# USBHUB.net
KiCad netlist of a schematic drawn in Altium Designer
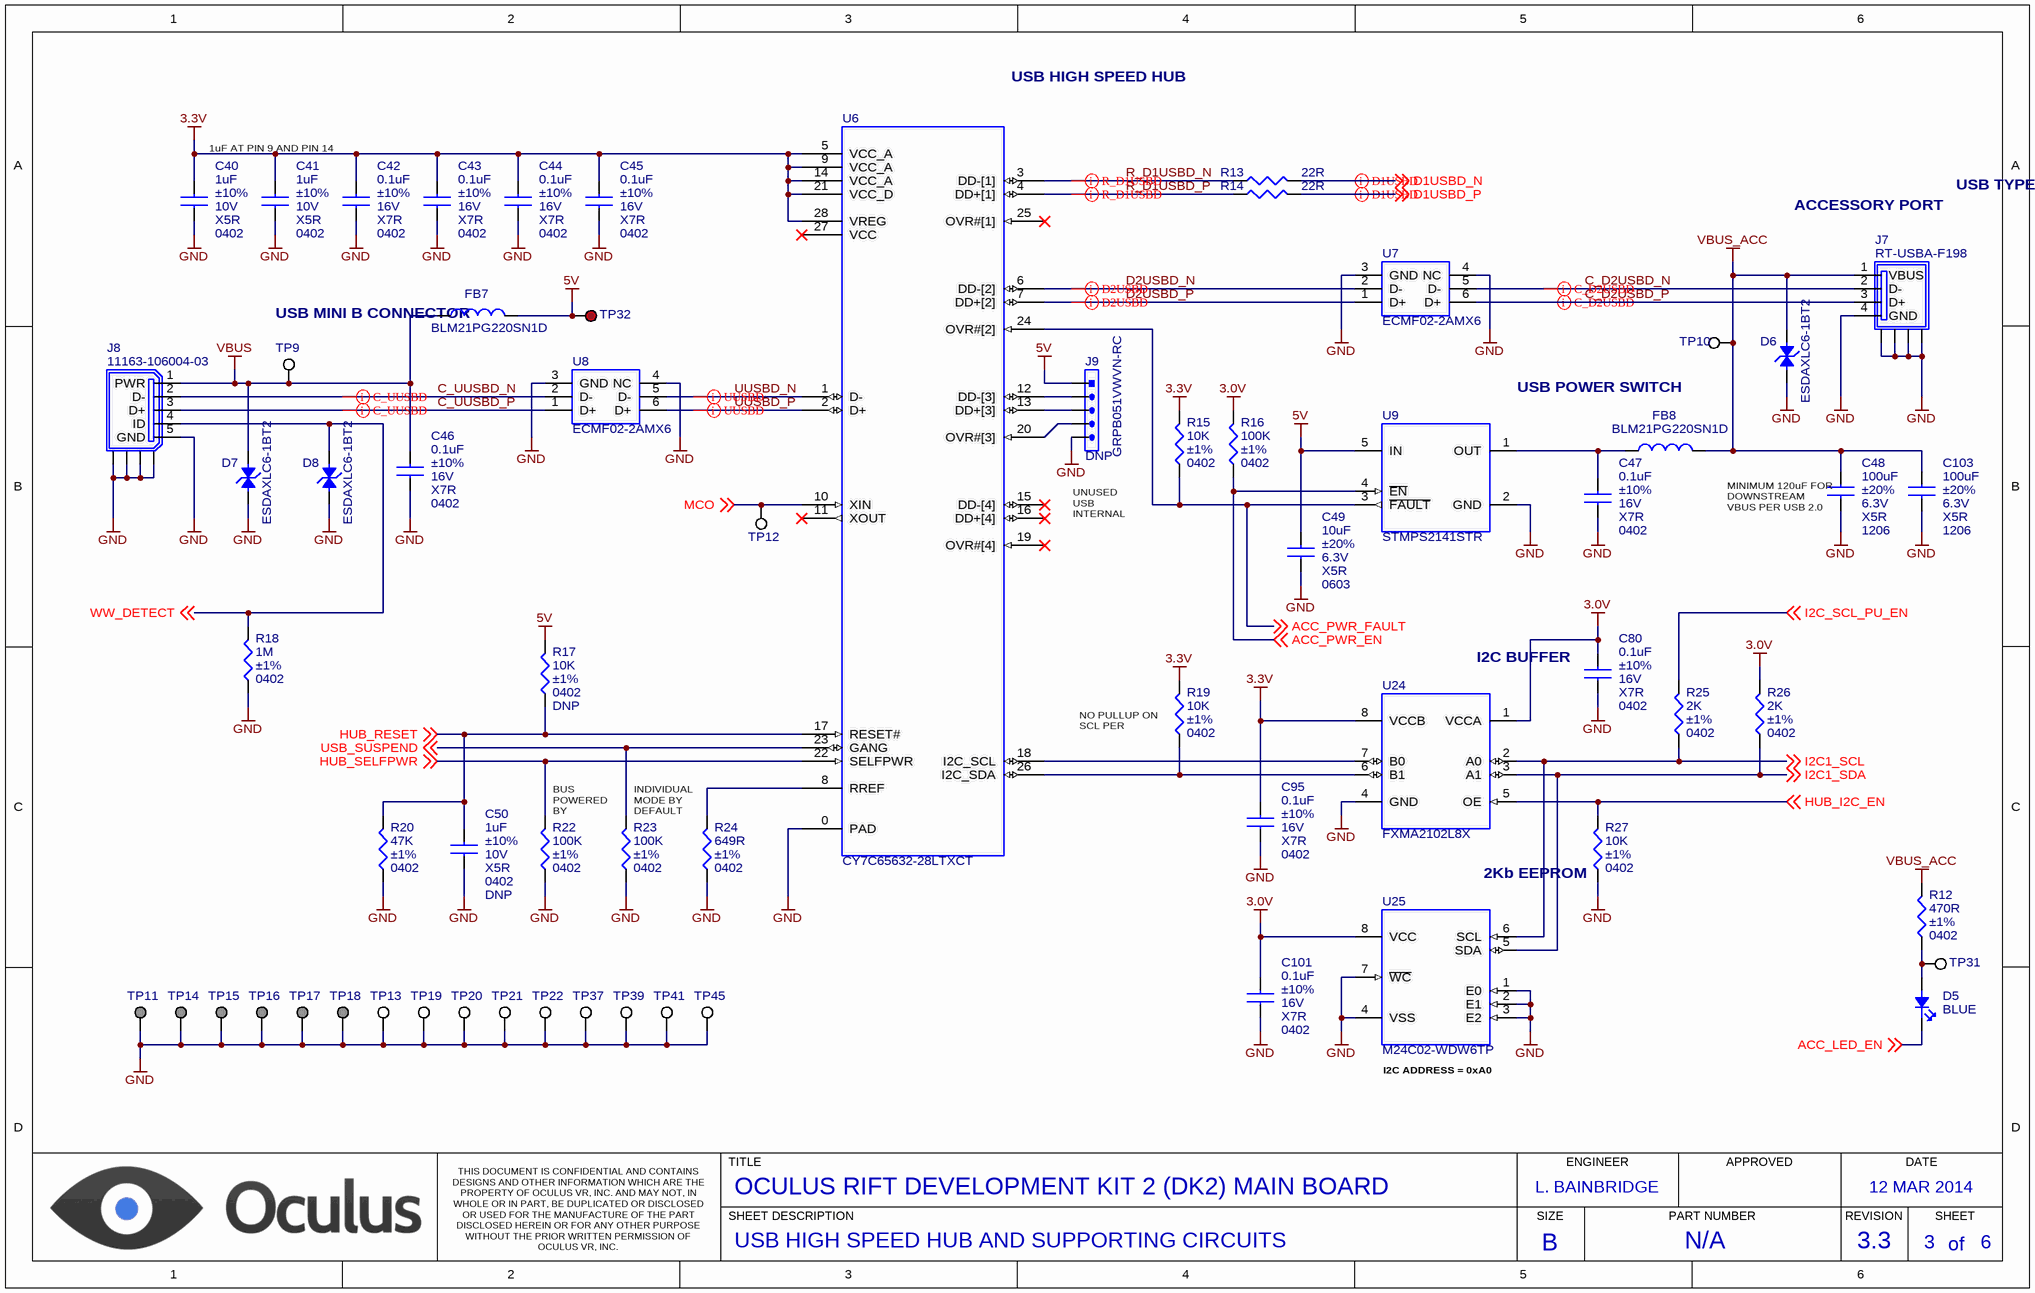
[diagram p0: USBHUB.SchDoc]

(export (version "E")
  (design (tool "Eeschema 10.0.6"))
  (components
    (comp (ref "C40")
      (value "1uF")
      (footprint "CAP_CERAMIC_0402")
      (description "CAP, CERAMIC, 1uF, ±10%, 10V, X5R, 0402")
      (fields
        (field (name "MANUFACTURER") "MURATA ELECTRONICS")
        (field (name "PART NUMBER") "GRM155R61A105KE15D")
        (field (name "TOLERANCE") "±10%")
        (field (name "VOLTAGE") "10V")
        (field (name "DIELECTRIC") "X5R")
        (field (name "PACKAGE") "0402")
      )
      (libsource (lib "DK2") (part "CAP, CERAMIC"))
    )
    (comp (ref "C41")
      (value "1uF")
      (footprint "CAP_CERAMIC_0402")
      (description "CAP, CERAMIC, 1uF, ±10%, 10V, X5R, 0402")
      (fields
        (field (name "MANUFACTURER") "MURATA ELECTRONICS")
        (field (name "PART NUMBER") "GRM155R61A105KE15D")
        (field (name "TOLERANCE") "±10%")
        (field (name "VOLTAGE") "10V")
        (field (name "DIELECTRIC") "X5R")
        (field (name "PACKAGE") "0402")
      )
      (libsource (lib "DK2") (part "CAP, CERAMIC"))
    )
    (comp (ref "C42")
      (value "0.1uF")
      (footprint "CAP_CERAMIC_0402")
      (description "CAP, CERAMIC, 0.1uF, ±10%, 16V, X7R, 0402")
      (fields
        (field (name "MANUFACTURER") "MURATA ELECTRONICS")
        (field (name "PART NUMBER") "GRM155R71C104KA88D")
        (field (name "TOLERANCE") "±10%")
        (field (name "VOLTAGE") "16V")
        (field (name "DIELECTRIC") "X7R")
        (field (name "PACKAGE") "0402")
      )
      (libsource (lib "DK2") (part "CAP, CERAMIC"))
    )
    (comp (ref "C43")
      (value "0.1uF")
      (footprint "CAP_CERAMIC_0402")
      (description "CAP, CERAMIC, 0.1uF, ±10%, 16V, X7R, 0402")
      (fields
        (field (name "MANUFACTURER") "MURATA ELECTRONICS")
        (field (name "PART NUMBER") "GRM155R71C104KA88D")
        (field (name "TOLERANCE") "±10%")
        (field (name "VOLTAGE") "16V")
        (field (name "DIELECTRIC") "X7R")
        (field (name "PACKAGE") "0402")
      )
      (libsource (lib "DK2") (part "CAP, CERAMIC"))
    )
    (comp (ref "C44")
      (value "0.1uF")
      (footprint "CAP_CERAMIC_0402")
      (description "CAP, CERAMIC, 0.1uF, ±10%, 16V, X7R, 0402")
      (fields
        (field (name "MANUFACTURER") "MURATA ELECTRONICS")
        (field (name "PART NUMBER") "GRM155R71C104KA88D")
        (field (name "TOLERANCE") "±10%")
        (field (name "VOLTAGE") "16V")
        (field (name "DIELECTRIC") "X7R")
        (field (name "PACKAGE") "0402")
      )
      (libsource (lib "DK2") (part "CAP, CERAMIC"))
    )
    (comp (ref "C45")
      (value "0.1uF")
      (footprint "CAP_CERAMIC_0402")
      (description "CAP, CERAMIC, 0.1uF, ±10%, 16V, X7R, 0402")
      (fields
        (field (name "MANUFACTURER") "MURATA ELECTRONICS")
        (field (name "PART NUMBER") "GRM155R71C104KA88D")
        (field (name "TOLERANCE") "±10%")
        (field (name "VOLTAGE") "16V")
        (field (name "DIELECTRIC") "X7R")
        (field (name "PACKAGE") "0402")
      )
      (libsource (lib "DK2") (part "CAP, CERAMIC"))
    )
    (comp (ref "C46")
      (value "0.1uF")
      (footprint "CAP_CERAMIC_0402")
      (description "CAP, CERAMIC, 0.1uF, ±10%, 16V, X7R, 0402")
      (fields
        (field (name "MANUFACTURER") "MURATA ELECTRONICS")
        (field (name "PART NUMBER") "GRM155R71C104KA88D")
        (field (name "TOLERANCE") "±10%")
        (field (name "VOLTAGE") "16V")
        (field (name "DIELECTRIC") "X7R")
        (field (name "PACKAGE") "0402")
      )
      (libsource (lib "DK2") (part "CAP, CERAMIC"))
    )
    (comp (ref "C47")
      (value "0.1uF")
      (footprint "CAP_CERAMIC_0402")
      (description "CAP, CERAMIC, 0.1uF, ±10%, 16V, X7R, 0402")
      (fields
        (field (name "MANUFACTURER") "MURATA ELECTRONICS")
        (field (name "PART NUMBER") "GRM155R71C104KA88D")
        (field (name "TOLERANCE") "±10%")
        (field (name "VOLTAGE") "16V")
        (field (name "DIELECTRIC") "X7R")
        (field (name "PACKAGE") "0402")
      )
      (libsource (lib "DK2") (part "CAP, CERAMIC"))
    )
    (comp (ref "C48")
      (value "100uF")
      (footprint "CAP_CERAMIC_1206")
      (description "CAP, CERAMIC, 100uF, ±20%, 6.3V, X5R, 1206")
      (fields
        (field (name "MANUFACTURER") "MURATA ELECTRONICS")
        (field (name "PART NUMBER") "GRM31CR60J107ME39K")
        (field (name "TOLERANCE") "±20%")
        (field (name "VOLTAGE") "6.3V")
        (field (name "DIELECTRIC") "X5R")
        (field (name "PACKAGE") "1206")
      )
      (libsource (lib "DK2") (part "CAP, CERAMIC"))
    )
    (comp (ref "C49")
      (value "10uF")
      (footprint "CAP_CERAMIC_0603")
      (description "CAP, CERAMIC, 10uF, ±20%, 6.3V, X5R, 0603")
      (fields
        (field (name "MANUFACTURER") "MURATA ELECTRONICS")
        (field (name "PART NUMBER") "GRM188R60J106ME47D")
        (field (name "TOLERANCE") "±20%")
        (field (name "VOLTAGE") "6.3V")
        (field (name "DIELECTRIC") "X5R")
        (field (name "PACKAGE") "0603")
      )
      (libsource (lib "DK2") (part "CAP, CERAMIC"))
    )
    (comp (ref "C50")
      (value "1uF")
      (footprint "CAP_CERAMIC_0402")
      (description "CAP, CERAMIC, 1uF, ±10%, 10V, X5R, 0402")
      (fields
        (field (name "MANUFACTURER") "MURATA ELECTRONICS")
        (field (name "PART NUMBER") "GRM155R61A105KE15D")
        (field (name "TOLERANCE") "±10%")
        (field (name "VOLTAGE") "10V")
        (field (name "DIELECTRIC") "X5R")
        (field (name "PACKAGE") "0402")
        (field (name "DNP") "DNP")
      )
      (libsource (lib "DK2") (part "CAP, CERAMIC"))
    )
    (comp (ref "C80")
      (value "0.1uF")
      (footprint "CAP_CERAMIC_0402")
      (description "CAP, CERAMIC, 0.1uF, ±10%, 16V, X7R, 0402")
      (fields
        (field (name "MANUFACTURER") "MURATA ELECTRONICS")
        (field (name "PART NUMBER") "GRM155R71C104KA88D")
        (field (name "TOLERANCE") "±10%")
        (field (name "VOLTAGE") "16V")
        (field (name "DIELECTRIC") "X7R")
        (field (name "PACKAGE") "0402")
      )
      (libsource (lib "DK2") (part "CAP, CERAMIC"))
    )
    (comp (ref "C95")
      (value "0.1uF")
      (footprint "CAP_CERAMIC_0402")
      (description "CAP, CERAMIC, 0.1uF, ±10%, 16V, X7R, 0402")
      (fields
        (field (name "MANUFACTURER") "MURATA ELECTRONICS")
        (field (name "PART NUMBER") "GRM155R71C104KA88D")
        (field (name "TOLERANCE") "±10%")
        (field (name "VOLTAGE") "16V")
        (field (name "DIELECTRIC") "X7R")
        (field (name "PACKAGE") "0402")
      )
      (libsource (lib "DK2") (part "CAP, CERAMIC"))
    )
    (comp (ref "C101")
      (value "0.1uF")
      (footprint "CAP_CERAMIC_0402")
      (description "CAP, CERAMIC, 0.1uF, ±10%, 16V, X7R, 0402")
      (fields
        (field (name "MANUFACTURER") "MURATA ELECTRONICS")
        (field (name "PART NUMBER") "GRM155R71C104KA88D")
        (field (name "TOLERANCE") "±10%")
        (field (name "VOLTAGE") "16V")
        (field (name "DIELECTRIC") "X7R")
        (field (name "PACKAGE") "0402")
      )
      (libsource (lib "DK2") (part "CAP, CERAMIC"))
    )
    (comp (ref "C103")
      (value "100uF")
      (footprint "CAP_CERAMIC_1206")
      (description "CAP, CERAMIC, 100uF, ±20%, 6.3V, X5R, 1206")
      (fields
        (field (name "MANUFACTURER") "MURATA ELECTRONICS")
        (field (name "PART NUMBER") "GRM31CR60J107ME39K")
        (field (name "TOLERANCE") "±20%")
        (field (name "VOLTAGE") "6.3V")
        (field (name "DIELECTRIC") "X5R")
        (field (name "PACKAGE") "1206")
      )
      (libsource (lib "DK2") (part "CAP, CERAMIC"))
    )
    (comp (ref "D5")
      (value "LED")
      (footprint "LED_BLUE_0603")
      (description "LED, BLUE, 0603")
      (fields
        (field (name "MANUFACTURER") "PANASONIC")
        (field (name "PART NUMBER") "LNJ926W8CRA")
        (field (name "COLOR") "BLUE")
      )
      (libsource (lib "DK2") (part "LED"))
    )
    (comp (ref "D6")
      (value "ESDAXLC6-1BT2")
      (footprint "SOD-882T")
      (description "DIODE, ESD SUPPRESSOR, SINGLE LINE BI-DIRECTIONAL, LOW CAPACITANCE")
      (fields (field (name "MANUFACTURER") "ST MICROELECTRONICS"))
      (libsource (lib "DK2") (part "ESDAXLC6-1BT2"))
    )
    (comp (ref "D7")
      (value "ESDAXLC6-1BT2")
      (footprint "SOD-882T")
      (description "DIODE, ESD SUPPRESSOR, SINGLE LINE BI-DIRECTIONAL, LOW CAPACITANCE")
      (fields (field (name "MANUFACTURER") "ST MICROELECTRONICS"))
      (libsource (lib "DK2") (part "ESDAXLC6-1BT2"))
    )
    (comp (ref "D8")
      (value "ESDAXLC6-1BT2")
      (footprint "SOD-882T")
      (description "DIODE, ESD SUPPRESSOR, SINGLE LINE BI-DIRECTIONAL, LOW CAPACITANCE")
      (fields (field (name "MANUFACTURER") "ST MICROELECTRONICS"))
      (libsource (lib "DK2") (part "ESDAXLC6-1BT2"))
    )
    (comp (ref "FB7")
      (value "BLM21PG220SN1D")
      (footprint "INDUCTOR_0805")
      (description "FERRITE CHIP BEAD, 22 OHM @ 100MHz, 6A, 0805")
      (fields (field (name "MANUFACTURER") "MURATA ELECTRONICS"))
      (libsource (lib "DK2") (part "INDUCTOR"))
    )
    (comp (ref "FB8")
      (value "BLM21PG220SN1D")
      (footprint "INDUCTOR_0805")
      (description "FERRITE CHIP BEAD, 22 OHM @ 100MHz, 6A, 0805")
      (fields (field (name "MANUFACTURER") "MURATA ELECTRONICS"))
      (libsource (lib "DK2") (part "INDUCTOR"))
    )
    (comp (ref "J7")
      (value "RT-USBA-F198")
      (footprint "RT-USBA-F198")
      (description "CONNECTOR, USB TYPE A RECEPTICLE, MID MOUNT")
      (fields (field (name "MANUFACTURER") "BERWAY TECHNOLOGY"))
      (libsource (lib "DK2") (part "RT-USBA-F198"))
    )
    (comp (ref "J8")
      (value "11163-106004-03")
      (footprint "BW_11163-106004-03")
      (description "CONNECTOR, USB MINI B, R/A, SMD")
      (fields (field (name "MANUFACTURER") "BERWAY TECHNOLOGY"))
      (libsource (lib "DK2") (part "BW_11163-106004-03"))
    )
    (comp (ref "J9")
      (value "GRPB051VWVN-RC")
      (footprint "GRPB051VWVN-RC")
      (description "CONNECTOR, HEADER, 1X5, 0.05\" PITCH")
      (fields (field (name "MANUFACTURER") "SULLINS CONNECTOR") (field (name "DNP") "DNP"))
      (libsource (lib "DK2") (part "GRPB051VWVN-RC"))
    )
    (comp (ref "R12")
      (value "470R")
      (footprint "RESISTOR_0402")
      (description "RES, 470 OHM, 1/10W, ±1%, 0402")
      (fields
        (field (name "MANUFACTURER") "PANASONIC")
        (field (name "PART NUMBER") "ERJ-2RKF4700X")
        (field (name "PACKAGE") "0402")
        (field (name "TOLERANCE") "±1%")
      )
      (libsource (lib "DK2") (part "RESISTOR"))
    )
    (comp (ref "R13")
      (value "22R")
      (footprint "RESISTOR_0402")
      (description "RES, 22 OHM, 1/10W, ±1%, 0402")
      (fields (field (name "MANUFACTURER") "PANASONIC") (field (name "PART NUMBER") "ERJ-2RKF22R0X"))
      (libsource (lib "DK2") (part "RESISTOR"))
    )
    (comp (ref "R14")
      (value "22R")
      (footprint "RESISTOR_0402")
      (description "RES, 22 OHM, 1/10W, ±1%, 0402")
      (fields (field (name "MANUFACTURER") "PANASONIC") (field (name "PART NUMBER") "ERJ-2RKF22R0X"))
      (libsource (lib "DK2") (part "RESISTOR"))
    )
    (comp (ref "R15")
      (value "10K")
      (footprint "RESISTOR_0402")
      (description "RES, 10K OHM, 1/10W, ±1%, 0402")
      (fields
        (field (name "MANUFACTURER") "PANASONIC")
        (field (name "PART NUMBER") "ERJ-2RKF1002X")
        (field (name "PACKAGE") "0402")
        (field (name "TOLERANCE") "±1%")
      )
      (libsource (lib "DK2") (part "RESISTOR"))
    )
    (comp (ref "R16")
      (value "100K")
      (footprint "RESISTOR_0402")
      (description "RES, 100K OHM, 1/10W, ±1%, 0402")
      (fields
        (field (name "MANUFACTURER") "PANASONIC")
        (field (name "PART NUMBER") "ERJ-2RKF1003X")
        (field (name "PACKAGE") "0402")
        (field (name "TOLERANCE") "±1%")
      )
      (libsource (lib "DK2") (part "RESISTOR"))
    )
    (comp (ref "R17")
      (value "10K")
      (footprint "RESISTOR_0402")
      (description "RES, 10K OHM, 1/10W, ±1%, 0402")
      (fields
        (field (name "MANUFACTURER") "PANASONIC")
        (field (name "PART NUMBER") "ERJ-2RKF1002X")
        (field (name "PACKAGE") "0402")
        (field (name "TOLERANCE") "±1%")
        (field (name "DNP") "DNP")
      )
      (libsource (lib "DK2") (part "RESISTOR"))
    )
    (comp (ref "R18")
      (value "1M")
      (footprint "RESISTOR_0402")
      (description "RES, 1M OHM, 1/10W, ±1%, 0402")
      (fields
        (field (name "MANUFACTURER") "PANASONIC")
        (field (name "PART NUMBER") "ERJ-2RKF1004X")
        (field (name "PACKAGE") "0402")
        (field (name "TOLERANCE") "±1%")
      )
      (libsource (lib "DK2") (part "RESISTOR"))
    )
    (comp (ref "R19")
      (value "10K")
      (footprint "RESISTOR_0402")
      (description "RES, 10K OHM, 1/10W, ±1%, 0402")
      (fields
        (field (name "MANUFACTURER") "PANASONIC")
        (field (name "PART NUMBER") "ERJ-2RKF1002X")
        (field (name "PACKAGE") "0402")
        (field (name "TOLERANCE") "±1%")
      )
      (libsource (lib "DK2") (part "RESISTOR"))
    )
    (comp (ref "R20")
      (value "47K")
      (footprint "RESISTOR_0402")
      (description "RES, 47K OHM, 1/10W, ±1%, 0402")
      (fields
        (field (name "MANUFACTURER") "PANASONIC")
        (field (name "PART NUMBER") "ERJ-2RKF4702X")
        (field (name "PACKAGE") "0402")
        (field (name "TOLERANCE") "±1%")
      )
      (libsource (lib "DK2") (part "RESISTOR"))
    )
    (comp (ref "R22")
      (value "100K")
      (footprint "RESISTOR_0402")
      (description "RES, 100K OHM, 1/10W, ±1%, 0402")
      (fields
        (field (name "MANUFACTURER") "PANASONIC")
        (field (name "PART NUMBER") "ERJ-2RKF1003X")
        (field (name "PACKAGE") "0402")
        (field (name "TOLERANCE") "±1%")
      )
      (libsource (lib "DK2") (part "RESISTOR"))
    )
    (comp (ref "R23")
      (value "100K")
      (footprint "RESISTOR_0402")
      (description "RES, 100K OHM, 1/10W, ±1%, 0402")
      (fields
        (field (name "MANUFACTURER") "PANASONIC")
        (field (name "PART NUMBER") "ERJ-2RKF1003X")
        (field (name "PACKAGE") "0402")
        (field (name "TOLERANCE") "±1%")
      )
      (libsource (lib "DK2") (part "RESISTOR"))
    )
    (comp (ref "R24")
      (value "649R")
      (footprint "RESISTOR_0402")
      (description "RES, 649 OHM, 1/10W, ±1%, 0402")
      (fields
        (field (name "MANUFACTURER") "PANASONIC")
        (field (name "PART NUMBER") "ERJ-2RKF6490X")
        (field (name "PACKAGE") "0402")
        (field (name "TOLERANCE") "±1%")
      )
      (libsource (lib "DK2") (part "RESISTOR"))
    )
    (comp (ref "R25")
      (value "2K")
      (footprint "RESISTOR_0402")
      (description "RES, 2K OHM, 1/10W, ±1%, 0402")
      (fields
        (field (name "MANUFACTURER") "PANASONIC")
        (field (name "PART NUMBER") "ERJ-2RKF2001X")
        (field (name "PACKAGE") "0402")
        (field (name "TOLERANCE") "±1%")
      )
      (libsource (lib "DK2") (part "RESISTOR"))
    )
    (comp (ref "R26")
      (value "2K")
      (footprint "RESISTOR_0402")
      (description "RES, 2K OHM, 1/10W, ±1%, 0402")
      (fields
        (field (name "MANUFACTURER") "PANASONIC")
        (field (name "PART NUMBER") "ERJ-2RKF2001X")
        (field (name "PACKAGE") "0402")
        (field (name "TOLERANCE") "±1%")
      )
      (libsource (lib "DK2") (part "RESISTOR"))
    )
    (comp (ref "R27")
      (value "10K")
      (footprint "RESISTOR_0402")
      (description "RES, 10K OHM, 1/10W, ±1%, 0402")
      (fields
        (field (name "MANUFACTURER") "PANASONIC")
        (field (name "PART NUMBER") "ERJ-2RKF1002X")
        (field (name "PACKAGE") "0402")
        (field (name "TOLERANCE") "±1%")
      )
      (libsource (lib "DK2") (part "RESISTOR"))
    )
    (comp (ref "TP9")
      (value "TEST POINT")
      (footprint "TEST_POINT_PAD_1.2X3MM")
      (libsource (lib "DK2") (part "TEST_POINT_GENERIC"))
    )
    (comp (ref "TP10")
      (value "TEST POINT")
      (footprint "TEST_POINT_PAD_1MM")
      (libsource (lib "DK2") (part "TEST_POINT_GENERIC"))
    )
    (comp (ref "TP11")
      (value "TEST POINT BLACK")
      (footprint "KS_5001_TEST_POINT_BLACK")
      (fields (field (name "MANUFACTURER") "KEYSTONE ELECTRONICS") (field (name "PART NUMBER") "5001"))
      (libsource (lib "DK2") (part "TEST_POINT_BLACK"))
    )
    (comp (ref "TP12")
      (value "TEST POINT")
      (footprint "TEST_POINT_PAD_1MM")
      (libsource (lib "DK2") (part "TEST_POINT_GENERIC"))
    )
    (comp (ref "TP13")
      (value "TEST POINT")
      (footprint "TEST_POINT_PAD_1.2X3MM")
      (libsource (lib "DK2") (part "TEST_POINT_GENERIC"))
    )
    (comp (ref "TP14")
      (value "TEST POINT BLACK")
      (footprint "KS_5001_TEST_POINT_BLACK")
      (fields (field (name "MANUFACTURER") "KEYSTONE ELECTRONICS") (field (name "PART NUMBER") "5001"))
      (libsource (lib "DK2") (part "TEST_POINT_BLACK"))
    )
    (comp (ref "TP15")
      (value "TEST POINT BLACK")
      (footprint "KS_5001_TEST_POINT_BLACK")
      (fields (field (name "MANUFACTURER") "KEYSTONE ELECTRONICS") (field (name "PART NUMBER") "5001"))
      (libsource (lib "DK2") (part "TEST_POINT_BLACK"))
    )
    (comp (ref "TP16")
      (value "TEST POINT BLACK")
      (footprint "KS_5001_TEST_POINT_BLACK")
      (fields (field (name "MANUFACTURER") "KEYSTONE ELECTRONICS") (field (name "PART NUMBER") "5001"))
      (libsource (lib "DK2") (part "TEST_POINT_BLACK"))
    )
    (comp (ref "TP17")
      (value "TEST POINT BLACK")
      (footprint "KS_5001_TEST_POINT_BLACK")
      (fields (field (name "MANUFACTURER") "KEYSTONE ELECTRONICS") (field (name "PART NUMBER") "5001"))
      (libsource (lib "DK2") (part "TEST_POINT_BLACK"))
    )
    (comp (ref "TP18")
      (value "TEST POINT BLACK")
      (footprint "KS_5001_TEST_POINT_BLACK")
      (fields (field (name "MANUFACTURER") "KEYSTONE ELECTRONICS") (field (name "PART NUMBER") "5001"))
      (libsource (lib "DK2") (part "TEST_POINT_BLACK"))
    )
    (comp (ref "TP19")
      (value "TEST POINT")
      (footprint "TEST_POINT_PAD_1MM")
      (libsource (lib "DK2") (part "TEST_POINT_GENERIC"))
    )
    (comp (ref "TP20")
      (value "TEST POINT")
      (footprint "TEST_POINT_PAD_1MM")
      (libsource (lib "DK2") (part "TEST_POINT_GENERIC"))
    )
    (comp (ref "TP21")
      (value "TEST POINT")
      (footprint "TEST_POINT_PAD_1MM")
      (libsource (lib "DK2") (part "TEST_POINT_GENERIC"))
    )
    (comp (ref "TP22")
      (value "TEST POINT")
      (footprint "TEST_POINT_PAD_1MM")
      (libsource (lib "DK2") (part "TEST_POINT_GENERIC"))
    )
    (comp (ref "TP31")
      (value "TEST POINT")
      (footprint "TEST_POINT_PAD_1MM")
      (libsource (lib "DK2") (part "TEST_POINT_GENERIC"))
    )
    (comp (ref "TP32")
      (value "TEST POINT RED")
      (footprint "KS_500X_TEST_POINT")
      (fields (field (name "MANUFACTURER") "KEYSTONE ELECTRONICS") (field (name "PART NUMBER") "5000"))
      (libsource (lib "DK2") (part "TEST_POINT_RED"))
    )
    (comp (ref "TP37")
      (value "TEST POINT")
      (footprint "TEST_POINT_PAD_1MM")
      (libsource (lib "DK2") (part "TEST_POINT_GENERIC"))
    )
    (comp (ref "TP39")
      (value "TEST POINT")
      (footprint "TEST_POINT_PAD_1MM")
      (libsource (lib "DK2") (part "TEST_POINT_GENERIC"))
    )
    (comp (ref "TP41")
      (value "TEST POINT")
      (footprint "TEST_POINT_PAD_1MM")
      (libsource (lib "DK2") (part "TEST_POINT_GENERIC"))
    )
    (comp (ref "TP45")
      (value "TEST POINT")
      (footprint "TEST_POINT_PAD_1MM")
      (libsource (lib "DK2") (part "TEST_POINT_GENERIC"))
    )
    (comp (ref "U6")
      (value "CY7C65632-28LTXCT")
      (footprint "QFN-28")
      (description "IC, USB 2.0 HUB CONTROLLER, 4-PORT, STT")
      (fields (field (name "MANUFACTURER") "CYPRESS SEMICONDUCTOR"))
      (libsource (lib "DK2") (part "CY7C65632-28LTXCT"))
    )
    (comp (ref "U7")
      (value "ECMF02-2AMX6")
      (footprint "UQFN-6L")
      (description "IC, COMMON MODE FILTER WITH ESD PROTECTION FOR MIPI")
      (fields (field (name "MANUFACTURER") "STMICROELECTRONICS"))
      (libsource (lib "DK2") (part "ECMF02-2AMX6"))
    )
    (comp (ref "U8")
      (value "ECMF02-2AMX6")
      (footprint "UQFN-6L")
      (description "IC, COMMON MODE FILTER WITH ESD PROTECTION FOR MIPI")
      (fields (field (name "MANUFACTURER") "STMICROELECTRONICS"))
      (libsource (lib "DK2") (part "ECMF02-2AMX6"))
    )
    (comp (ref "U9")
      (value "STMPS2141STR")
      (footprint "SOT23-5L")
      (description "IC, USB POWER DISTRIBUTION SWITCH, 500mA CURRENT LIMIT")
      (fields (field (name "MANUFACTURER") "STMICROELECTRONICS"))
      (libsource (lib "DK2") (part "STMPS2141STR"))
    )
    (comp (ref "U24")
      (value "FXMA2102L8X")
      (footprint "UFQFN-8")
      (description "IC, I2C TRANSLATOR, BUFFER AND REPEATER")
      (fields (field (name "MANUFACTURER") "FAIRCHILD SEMICONDUCTOR"))
      (libsource (lib "DK2") (part "FXMA2102L8X"))
    )
    (comp (ref "U25")
      (value "M24C02-WDW6TP")
      (footprint "TSSOP8")
      (description "IC, EEPROM, I2C, 2kB")
      (fields (field (name "MANUFACTURER") "STMICROELECTRONICS"))
      (libsource (lib "DK2") (part "M24C02-WDW6TP"))
    )
  )
  (nets
    (net (code "1") (name "/C_D2USBD_N") (class "Default")
      (node (ref "J7") (pin "2") (pinfunction "D-_2") (pintype "tri_state"))
      (node (ref "U7") (pin "5") (pinfunction "D-_5") (pintype "passive"))
    )
    (net (code "2") (name "/C_D2USBD_P") (class "Default")
      (node (ref "J7") (pin "3") (pinfunction "D+_3") (pintype "tri_state"))
      (node (ref "U7") (pin "6") (pinfunction "D+_6") (pintype "passive"))
    )
    (net (code "3") (name "/C_UUSBD_N") (class "Default")
      (node (ref "J8") (pin "2") (pinfunction "D-_2") (pintype "tri_state"))
      (node (ref "U8") (pin "2") (pinfunction "D-_2") (pintype "passive"))
    )
    (net (code "4") (name "/C_UUSBD_P") (class "Default")
      (node (ref "J8") (pin "3") (pinfunction "D+_3") (pintype "tri_state"))
      (node (ref "U8") (pin "1") (pinfunction "D+_1") (pintype "passive"))
    )
    (net (code "5") (name "/D2USBD_N") (class "Default")
      (node (ref "U6") (pin "6") (pinfunction "DD-[2]_6") (pintype "bidirectional"))
      (node (ref "U7") (pin "2") (pinfunction "D-_2") (pintype "passive"))
    )
    (net (code "6") (name "/D2USBD_P") (class "Default")
      (node (ref "U6") (pin "7") (pinfunction "DD+[2]_7") (pintype "bidirectional"))
      (node (ref "U7") (pin "1") (pinfunction "D+_1") (pintype "passive"))
    )
    (net (code "7") (name "/R_D1USBD_N") (class "Default")
      (node (ref "R13") (pin "1") (pinfunction "1_1") (pintype "passive"))
      (node (ref "U6") (pin "3") (pinfunction "DD-[1]_3") (pintype "bidirectional"))
    )
    (net (code "8") (name "/R_D1USBD_P") (class "Default")
      (node (ref "R14") (pin "1") (pinfunction "1_1") (pintype "passive"))
      (node (ref "U6") (pin "4") (pinfunction "DD+[1]_4") (pintype "bidirectional"))
    )
    (net (code "9") (name "/UUSBD_N") (class "Default")
      (node (ref "U6") (pin "1") (pinfunction "D-_1") (pintype "bidirectional"))
      (node (ref "U8") (pin "5") (pinfunction "D-_5") (pintype "passive"))
    )
    (net (code "10") (name "/UUSBD_P") (class "Default")
      (node (ref "U6") (pin "2") (pinfunction "D+_2") (pintype "bidirectional"))
      (node (ref "U8") (pin "6") (pinfunction "D+_6") (pintype "passive"))
    )
    (net (code "11") (name "3.0V") (class "Default")
      (node (ref "C101") (pin "1") (pinfunction "1_1") (pintype "passive"))
      (node (ref "C80") (pin "1") (pinfunction "1_1") (pintype "passive"))
      (node (ref "R16") (pin "2") (pinfunction "2_2") (pintype "passive"))
      (node (ref "R26") (pin "2") (pinfunction "2_2") (pintype "passive"))
      (node (ref "U24") (pin "1") (pinfunction "VCCA_1") (pintype "power_in"))
      (node (ref "U25") (pin "8") (pinfunction "VCC_8") (pintype "power_in"))
    )
    (net (code "12") (name "3.3V") (class "Default")
      (node (ref "C40") (pin "1") (pinfunction "1_1") (pintype "passive"))
      (node (ref "C41") (pin "1") (pinfunction "1_1") (pintype "passive"))
      (node (ref "C42") (pin "1") (pinfunction "1_1") (pintype "passive"))
      (node (ref "C43") (pin "1") (pinfunction "1_1") (pintype "passive"))
      (node (ref "C44") (pin "1") (pinfunction "1_1") (pintype "passive"))
      (node (ref "C45") (pin "1") (pinfunction "1_1") (pintype "passive"))
      (node (ref "C95") (pin "1") (pinfunction "1_1") (pintype "passive"))
      (node (ref "R15") (pin "2") (pinfunction "2_2") (pintype "passive"))
      (node (ref "R19") (pin "2") (pinfunction "2_2") (pintype "passive"))
      (node (ref "U24") (pin "8") (pinfunction "VCCB_8") (pintype "power_in"))
      (node (ref "U6") (pin "14") (pinfunction "VCC_A_14") (pintype "power_in"))
      (node (ref "U6") (pin "21") (pinfunction "VCC_D_21") (pintype "power_in"))
      (node (ref "U6") (pin "28") (pinfunction "VREG_28") (pintype "power_in"))
      (node (ref "U6") (pin "5") (pinfunction "VCC_A_5") (pintype "power_in"))
      (node (ref "U6") (pin "9") (pinfunction "VCC_A_9") (pintype "power_in"))
    )
    (net (code "13") (name "5V") (class "Default")
      (node (ref "C49") (pin "1") (pinfunction "1_1") (pintype "passive"))
      (node (ref "FB7") (pin "2") (pinfunction "2_2") (pintype "passive"))
      (node (ref "J9") (pin "1") (pintype "passive"))
      (node (ref "R17") (pin "2") (pinfunction "2_2") (pintype "passive"))
      (node (ref "TP32") (pin "1") (pinfunction "1_1") (pintype "passive"))
      (node (ref "U9") (pin "5") (pinfunction "IN_5") (pintype "power_in"))
    )
    (net (code "14") (name "ACC_LED_EN") (class "Default")
      (node (ref "D5") (pin "2") (pinfunction "K_2") (pintype "passive"))
    )
    (net (code "15") (name "ACC_PWR_EN") (class "Default")
      (node (ref "R16") (pin "1") (pinfunction "1_1") (pintype "passive"))
      (node (ref "U9") (pin "4") (pinfunction "~{EN}_4") (pintype "input"))
    )
    (net (code "16") (name "ACC_PWR_FAULT") (class "Default")
      (node (ref "R15") (pin "1") (pinfunction "1_1") (pintype "passive"))
      (node (ref "U6") (pin "24") (pinfunction "OVR#[2]_24") (pintype "input"))
      (node (ref "U9") (pin "3") (pinfunction "~{FAULT}_3") (pintype "output"))
    )
    (net (code "17") (name "D1USBD_N") (class "Default")
      (node (ref "R13") (pin "2") (pinfunction "2_2") (pintype "passive"))
    )
    (net (code "18") (name "D1USBD_P") (class "Default")
      (node (ref "R14") (pin "2") (pinfunction "2_2") (pintype "passive"))
    )
    (net (code "19") (name "GND") (class "Default")
      (node (ref "C101") (pin "2") (pinfunction "2_2") (pintype "passive"))
      (node (ref "C103") (pin "2") (pinfunction "2_2") (pintype "passive"))
      (node (ref "C40") (pin "2") (pinfunction "2_2") (pintype "passive"))
      (node (ref "C41") (pin "2") (pinfunction "2_2") (pintype "passive"))
      (node (ref "C42") (pin "2") (pinfunction "2_2") (pintype "passive"))
      (node (ref "C43") (pin "2") (pinfunction "2_2") (pintype "passive"))
      (node (ref "C44") (pin "2") (pinfunction "2_2") (pintype "passive"))
      (node (ref "C45") (pin "2") (pinfunction "2_2") (pintype "passive"))
      (node (ref "C46") (pin "2") (pinfunction "2_2") (pintype "passive"))
      (node (ref "C47") (pin "2") (pinfunction "2_2") (pintype "passive"))
      (node (ref "C48") (pin "2") (pinfunction "2_2") (pintype "passive"))
      (node (ref "C49") (pin "2") (pinfunction "2_2") (pintype "passive"))
      (node (ref "C50") (pin "2") (pinfunction "2_2") (pintype "passive"))
      (node (ref "C80") (pin "2") (pinfunction "2_2") (pintype "passive"))
      (node (ref "C95") (pin "2") (pinfunction "2_2") (pintype "passive"))
      (node (ref "D6") (pin "2") (pintype "passive"))
      (node (ref "D7") (pin "2") (pintype "passive"))
      (node (ref "D8") (pin "2") (pintype "passive"))
      (node (ref "J7") (pin "4") (pinfunction "GND_4") (pintype "passive"))
      (node (ref "J7") (pin "5") (pinfunction "SHIELD_5") (pintype "passive"))
      (node (ref "J7") (pin "6") (pinfunction "SHIELD_6") (pintype "passive"))
      (node (ref "J7") (pin "7") (pinfunction "SHIELD_7") (pintype "passive"))
      (node (ref "J7") (pin "8") (pinfunction "SHIELD_8") (pintype "passive"))
      (node (ref "J8") (pin "5") (pinfunction "GND_5") (pintype "power_in"))
      (node (ref "J8") (pin "6") (pinfunction "SHIELD_6") (pintype "passive"))
      (node (ref "J8") (pin "7") (pinfunction "SHIELD_7") (pintype "passive"))
      (node (ref "J8") (pin "8") (pinfunction "SHIELD_8") (pintype "passive"))
      (node (ref "J8") (pin "9") (pinfunction "SHIELD_9") (pintype "passive"))
      (node (ref "J9") (pin "5") (pintype "passive"))
      (node (ref "R18") (pin "1") (pinfunction "1_1") (pintype "passive"))
      (node (ref "R20") (pin "1") (pinfunction "1_1") (pintype "passive"))
      (node (ref "R22") (pin "1") (pinfunction "1_1") (pintype "passive"))
      (node (ref "R23") (pin "1") (pinfunction "1_1") (pintype "passive"))
      (node (ref "R24") (pin "1") (pinfunction "1_1") (pintype "passive"))
      (node (ref "R27") (pin "1") (pinfunction "1_1") (pintype "passive"))
      (node (ref "TP11") (pin "1") (pinfunction "1_1") (pintype "passive"))
      (node (ref "TP13") (pin "1") (pinfunction "1_1") (pintype "passive"))
      (node (ref "TP14") (pin "1") (pinfunction "1_1") (pintype "passive"))
      (node (ref "TP15") (pin "1") (pinfunction "1_1") (pintype "passive"))
      (node (ref "TP16") (pin "1") (pinfunction "1_1") (pintype "passive"))
      (node (ref "TP17") (pin "1") (pinfunction "1_1") (pintype "passive"))
      (node (ref "TP18") (pin "1") (pinfunction "1_1") (pintype "passive"))
      (node (ref "TP19") (pin "1") (pinfunction "1_1") (pintype "passive"))
      (node (ref "TP20") (pin "1") (pinfunction "1_1") (pintype "passive"))
      (node (ref "TP21") (pin "1") (pinfunction "1_1") (pintype "passive"))
      (node (ref "TP22") (pin "1") (pinfunction "1_1") (pintype "passive"))
      (node (ref "TP37") (pin "1") (pinfunction "1_1") (pintype "passive"))
      (node (ref "TP39") (pin "1") (pinfunction "1_1") (pintype "passive"))
      (node (ref "TP41") (pin "1") (pinfunction "1_1") (pintype "passive"))
      (node (ref "TP45") (pin "1") (pinfunction "1_1") (pintype "passive"))
      (node (ref "U24") (pin "4") (pinfunction "GND_4") (pintype "power_in"))
      (node (ref "U25") (pin "1") (pinfunction "E0_1") (pintype "input"))
      (node (ref "U25") (pin "2") (pinfunction "E1_2") (pintype "input"))
      (node (ref "U25") (pin "3") (pinfunction "E2_3") (pintype "input"))
      (node (ref "U25") (pin "4") (pinfunction "VSS_4") (pintype "power_in"))
      (node (ref "U25") (pin "7") (pinfunction "~{WC}_7") (pintype "input"))
      (node (ref "U6") (pin "0") (pinfunction "PAD_0") (pintype "power_in"))
      (node (ref "U7") (pin "3") (pinfunction "GND_3") (pintype "power_in"))
      (node (ref "U7") (pin "4") (pinfunction "NC_4") (pintype "power_in"))
      (node (ref "U8") (pin "3") (pinfunction "GND_3") (pintype "power_in"))
      (node (ref "U8") (pin "4") (pinfunction "NC_4") (pintype "power_in"))
      (node (ref "U9") (pin "2") (pinfunction "GND_2") (pintype "power_in"))
    )
    (net (code "20") (name "HUB_I2C_EN") (class "Default")
      (node (ref "R27") (pin "2") (pinfunction "2_2") (pintype "passive"))
      (node (ref "U24") (pin "5") (pinfunction "OE_5") (pintype "input"))
    )
    (net (code "21") (name "HUB_RESET") (class "Default")
      (node (ref "C50") (pin "1") (pinfunction "1_1") (pintype "passive"))
      (node (ref "R17") (pin "1") (pinfunction "1_1") (pintype "passive"))
      (node (ref "R20") (pin "2") (pinfunction "2_2") (pintype "passive"))
      (node (ref "U6") (pin "17") (pinfunction "RESET#_17") (pintype "input"))
    )
    (net (code "22") (name "HUB_SELFPWR") (class "Default")
      (node (ref "R22") (pin "2") (pinfunction "2_2") (pintype "passive"))
      (node (ref "U6") (pin "22") (pinfunction "SELFPWR_22") (pintype "input"))
    )
    (net (code "23") (name "I2C1_SCL") (class "Default")
      (node (ref "R25") (pin "1") (pinfunction "1_1") (pintype "passive"))
      (node (ref "U24") (pin "2") (pinfunction "A0_2") (pintype "bidirectional"))
      (node (ref "U25") (pin "6") (pinfunction "SCL_6") (pintype "input"))
    )
    (net (code "24") (name "I2C1_SDA") (class "Default")
      (node (ref "R26") (pin "1") (pinfunction "1_1") (pintype "passive"))
      (node (ref "U24") (pin "3") (pinfunction "A1_3") (pintype "bidirectional"))
      (node (ref "U25") (pin "5") (pinfunction "SDA_5") (pintype "bidirectional"))
    )
    (net (code "25") (name "I2C_SCL_PU_EN") (class "Default")
      (node (ref "R25") (pin "2") (pinfunction "2_2") (pintype "passive"))
    )
    (net (code "26") (name "MCO") (class "Default")
      (node (ref "TP12") (pin "1") (pinfunction "1_1") (pintype "passive"))
      (node (ref "U6") (pin "10") (pinfunction "XIN_10") (pintype "input"))
    )
    (net (code "27") (name "Net-(D5-A)") (class "Default")
      (node (ref "D5") (pin "1") (pinfunction "A_1") (pintype "passive"))
      (node (ref "R12") (pin "1") (pinfunction "1_1") (pintype "passive"))
      (node (ref "TP31") (pin "1") (pinfunction "1_1") (pintype "passive"))
    )
    (net (code "28") (name "Net-(U6-DD+[3])") (class "Default")
      (node (ref "J9") (pin "3") (pintype "passive"))
      (node (ref "U6") (pin "13") (pinfunction "DD+[3]_13") (pintype "bidirectional"))
    )
    (net (code "29") (name "Net-(U6-DD-[3])") (class "Default")
      (node (ref "J9") (pin "2") (pintype "passive"))
      (node (ref "U6") (pin "12") (pinfunction "DD-[3]_12") (pintype "bidirectional"))
    )
    (net (code "30") (name "Net-(U6-OVR#[3])") (class "Default")
      (node (ref "J9") (pin "4") (pintype "passive"))
      (node (ref "U6") (pin "20") (pinfunction "OVR#[3]_20") (pintype "input"))
    )
    (net (code "31") (name "Net-(U6-RREF)") (class "Default")
      (node (ref "R24") (pin "2") (pinfunction "2_2") (pintype "passive"))
      (node (ref "U6") (pin "8") (pinfunction "RREF_8") (pintype "passive"))
    )
    (net (code "32") (name "Net-(U9-OUT)") (class "Default")
      (node (ref "C47") (pin "1") (pinfunction "1_1") (pintype "passive"))
      (node (ref "FB8") (pin "1") (pinfunction "1_1") (pintype "passive"))
      (node (ref "U9") (pin "1") (pinfunction "OUT_1") (pintype "power_in"))
    )
    (net (code "33") (name "Net-(U24-B0)") (class "Default")
      (node (ref "U24") (pin "7") (pinfunction "B0_7") (pintype "bidirectional"))
      (node (ref "U6") (pin "18") (pinfunction "I2C_SCL_18") (pintype "bidirectional"))
    )
    (net (code "34") (name "Net-(U24-B1)") (class "Default")
      (node (ref "R19") (pin "1") (pinfunction "1_1") (pintype "passive"))
      (node (ref "U24") (pin "6") (pinfunction "B1_6") (pintype "bidirectional"))
      (node (ref "U6") (pin "26") (pinfunction "I2C_SDA_26") (pintype "bidirectional"))
    )
    (net (code "35") (name "USB_SUSPEND") (class "Default")
      (node (ref "R23") (pin "2") (pinfunction "2_2") (pintype "passive"))
      (node (ref "U6") (pin "23") (pinfunction "GANG_23") (pintype "bidirectional"))
    )
    (net (code "36") (name "VBUS") (class "Default")
      (node (ref "C46") (pin "1") (pinfunction "1_1") (pintype "passive"))
      (node (ref "D7") (pin "1") (pintype "passive"))
      (node (ref "FB7") (pin "1") (pinfunction "1_1") (pintype "passive"))
      (node (ref "J8") (pin "1") (pinfunction "PWR_1") (pintype "power_in"))
      (node (ref "TP9") (pin "1") (pinfunction "1_1") (pintype "passive"))
    )
    (net (code "37") (name "VBUS_ACC") (class "Default")
      (node (ref "C103") (pin "1") (pinfunction "1_1") (pintype "passive"))
      (node (ref "C48") (pin "1") (pinfunction "1_1") (pintype "passive"))
      (node (ref "D6") (pin "1") (pintype "passive"))
      (node (ref "FB8") (pin "2") (pinfunction "2_2") (pintype "passive"))
      (node (ref "J7") (pin "1") (pinfunction "VBUS_1") (pintype "power_in"))
      (node (ref "R12") (pin "2") (pinfunction "2_2") (pintype "passive"))
      (node (ref "TP10") (pin "1") (pinfunction "1_1") (pintype "passive"))
    )
    (net (code "38") (name "WW_DETECT") (class "Default")
      (node (ref "D8") (pin "1") (pintype "passive"))
      (node (ref "J8") (pin "4") (pinfunction "ID_4") (pintype "passive"))
      (node (ref "R18") (pin "2") (pinfunction "2_2") (pintype "passive"))
    )
    (net (code "39") (name "unconnected-(U6-DD+[4]-Pad16)") (class "Default")
      (node (ref "U6") (pin "16") (pinfunction "DD+[4]_16") (pintype "bidirectional+no_connect"))
    )
    (net (code "40") (name "unconnected-(U6-DD-[4]-Pad15)") (class "Default")
      (node (ref "U6") (pin "15") (pinfunction "DD-[4]_15") (pintype "bidirectional+no_connect"))
    )
    (net (code "41") (name "unconnected-(U6-OVR#[1]-Pad25)") (class "Default")
      (node (ref "U6") (pin "25") (pinfunction "OVR#[1]_25") (pintype "input+no_connect"))
    )
    (net (code "42") (name "unconnected-(U6-OVR#[4]-Pad19)") (class "Default")
      (node (ref "U6") (pin "19") (pinfunction "OVR#[4]_19") (pintype "input+no_connect"))
    )
    (net (code "43") (name "unconnected-(U6-VCC-Pad27)") (class "Default")
      (node (ref "U6") (pin "27") (pinfunction "VCC_27") (pintype "power_in+no_connect"))
    )
    (net (code "44") (name "unconnected-(U6-XOUT-Pad11)") (class "Default")
      (node (ref "U6") (pin "11") (pinfunction "XOUT_11") (pintype "output+no_connect"))
    )
  )
)
